# Cell_Temp_Controller_v1_0.net
KiCad netlist of a schematic drawn in EAGLE
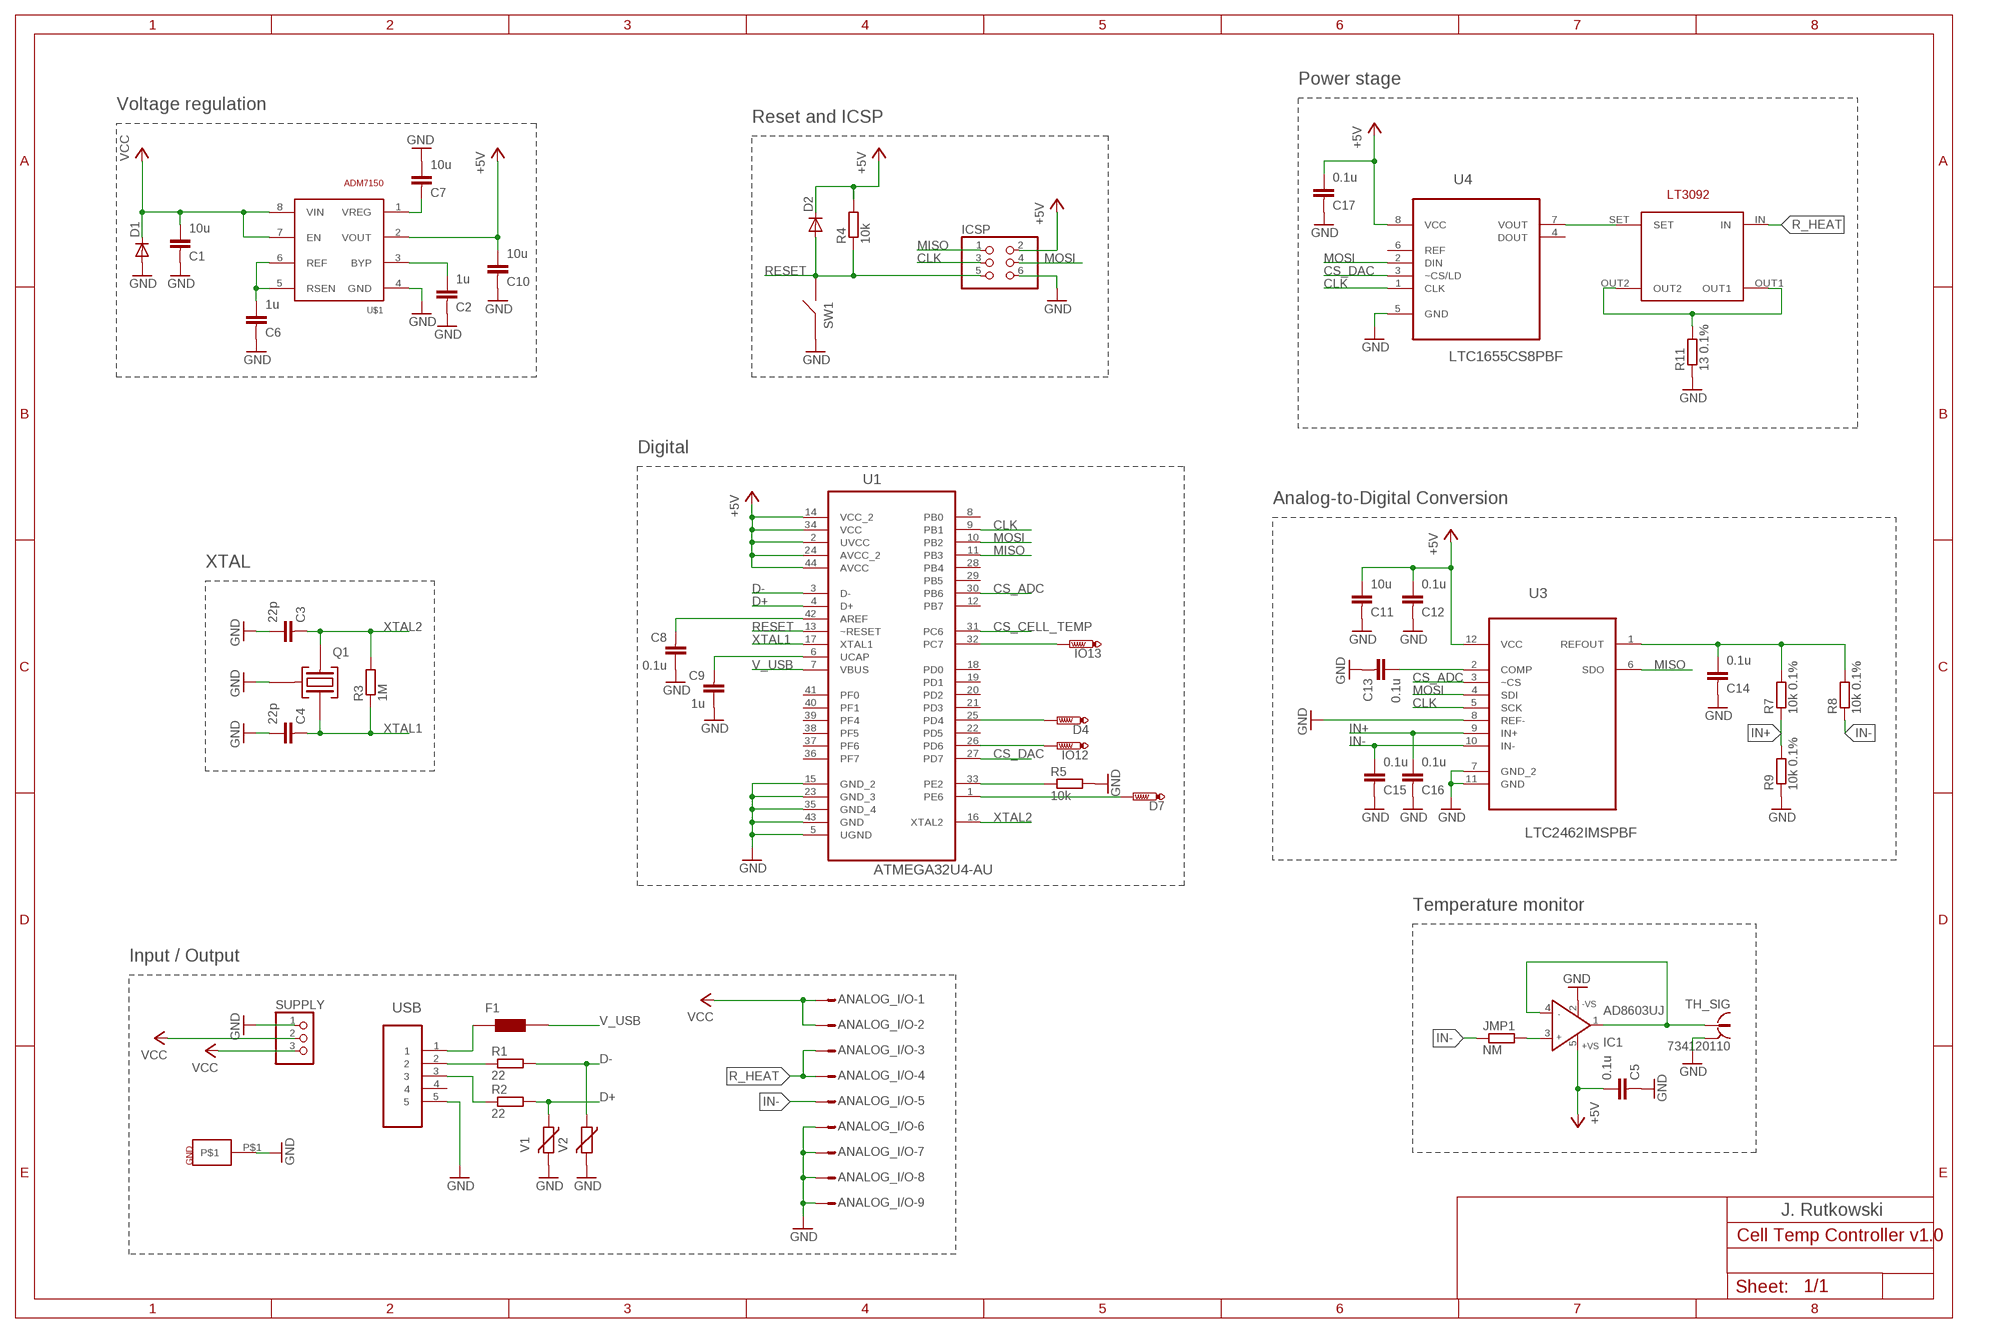
[diagram p0: schematic, sheet 1]

(export (version "E")
  (design (tool "Eeschema 10.0.6"))
  (components
    (comp (ref "ANALOG_I/O")
      (value "M09HPS")
      (footprint "eagle-import:M09HP")
      (libsource (lib "eagle-import") (part "M09?SHP"))
    )
    (comp (ref "C1")
      (value "10u")
      (footprint "eagle-import:C0603K")
      (libsource (lib "eagle-import") (part "C-EUC0603K"))
    )
    (comp (ref "C2")
      (value "1u")
      (footprint "eagle-import:C0603K")
      (libsource (lib "eagle-import") (part "C-EUC0603K"))
    )
    (comp (ref "C3")
      (value "22p")
      (footprint "eagle-import:C0603K")
      (libsource (lib "eagle-import") (part "C-EUC0603K"))
    )
    (comp (ref "C4")
      (value "22p")
      (footprint "eagle-import:C0603K")
      (libsource (lib "eagle-import") (part "C-EUC0603K"))
    )
    (comp (ref "C5")
      (value "0.1u")
      (footprint "eagle-import:C0603K")
      (libsource (lib "eagle-import") (part "C-EUC0603K"))
    )
    (comp (ref "C6")
      (value "1u")
      (footprint "eagle-import:C0603K")
      (libsource (lib "eagle-import") (part "C-EUC0603K"))
    )
    (comp (ref "C7")
      (value "10u")
      (footprint "eagle-import:C0603K")
      (libsource (lib "eagle-import") (part "C-EUC0603K"))
    )
    (comp (ref "C8")
      (value "0.1u")
      (footprint "eagle-import:C0603K")
      (libsource (lib "eagle-import") (part "C-EUC0603K"))
    )
    (comp (ref "C9")
      (value "1u")
      (footprint "eagle-import:C0603K")
      (libsource (lib "eagle-import") (part "C-EUC0603K"))
    )
    (comp (ref "C10")
      (value "10u")
      (footprint "eagle-import:C0603K")
      (libsource (lib "eagle-import") (part "C-EUC0603K"))
    )
    (comp (ref "C11")
      (value "10u")
      (footprint "eagle-import:C0603K")
      (libsource (lib "eagle-import") (part "C-EUC0603K"))
    )
    (comp (ref "C12")
      (value "0.1u")
      (footprint "eagle-import:C0603K")
      (libsource (lib "eagle-import") (part "C-EUC0603K"))
    )
    (comp (ref "C13")
      (value "0.1u")
      (footprint "eagle-import:C0603K")
      (libsource (lib "eagle-import") (part "C-EUC0603K"))
    )
    (comp (ref "C14")
      (value "0.1u")
      (footprint "eagle-import:C0603K")
      (libsource (lib "eagle-import") (part "C-EUC0603K"))
    )
    (comp (ref "C15")
      (value "0.1u")
      (footprint "eagle-import:C0603K")
      (libsource (lib "eagle-import") (part "C-EUC0603K"))
    )
    (comp (ref "C16")
      (value "0.1u")
      (footprint "eagle-import:C0603K")
      (libsource (lib "eagle-import") (part "C-EUC0603K"))
    )
    (comp (ref "C17")
      (value "0.1u")
      (footprint "eagle-import:C0603K")
      (libsource (lib "eagle-import") (part "C-EUC0603K"))
    )
    (comp (ref "D1")
      (value "DIODE-SOD123")
      (footprint "eagle-import:SOD123")
      (libsource (lib "eagle-import") (part "DIODE-SOD123"))
    )
    (comp (ref "D2")
      (value "DIODE-SOD123")
      (footprint "eagle-import:SOD123")
      (libsource (lib "eagle-import") (part "DIODE-SOD123"))
    )
    (comp (ref "D4")
      (value "PTR1PAD1-13")
      (footprint "eagle-import:P1-13")
      (libsource (lib "eagle-import") (part "PTR1PAD1-13"))
    )
    (comp (ref "D7")
      (value "PTR1PAD1-13")
      (footprint "eagle-import:P1-13")
      (libsource (lib "eagle-import") (part "PTR1PAD1-13"))
    )
    (comp (ref "F1")
      (value "FUSE")
      (footprint "eagle-import:C1812")
      (libsource (lib "eagle-import") (part "FUSE"))
    )
    (comp (ref "IC1")
      (value "AD8603UJ")
      (footprint "eagle-import:SOT23-5")
      (fields (field (name "MF") "ALTERA CORPORATION") (field (name "MPN") "AD8603AUJZ-REEL7"))
      (libsource (lib "eagle-import") (part "AD8603UJ"))
    )
    (comp (ref "ICSP")
      (value "PINHD-2X3")
      (footprint "eagle-import:2X03")
      (libsource (lib "eagle-import") (part "PINHD-2X3"))
    )
    (comp (ref "IO12")
      (value "PTR1PAD1-13")
      (footprint "eagle-import:P1-13")
      (libsource (lib "eagle-import") (part "PTR1PAD1-13"))
    )
    (comp (ref "IO13")
      (value "PTR1PAD1-13")
      (footprint "eagle-import:P1-13")
      (libsource (lib "eagle-import") (part "PTR1PAD1-13"))
    )
    (comp (ref "JMP1")
      (value "NM")
      (footprint "eagle-import:R0402")
      (libsource (lib "eagle-import") (part "R-EU_R0402"))
    )
    (comp (ref "Q1")
      (value "CX2520SB")
      (footprint "eagle-import:QUARTZ")
      (fields (field (name "MPN") "CX5032SB16000F0FLJZZ"))
      (libsource (lib "eagle-import") (part "CX2520SB"))
    )
    (comp (ref "R1")
      (value "22")
      (footprint "eagle-import:R0603")
      (libsource (lib "eagle-import") (part "R-EU_R0603"))
    )
    (comp (ref "R2")
      (value "22")
      (footprint "eagle-import:R0603")
      (libsource (lib "eagle-import") (part "R-EU_R0603"))
    )
    (comp (ref "R3")
      (value "1M")
      (footprint "eagle-import:R0603")
      (libsource (lib "eagle-import") (part "R-EU_R0603"))
    )
    (comp (ref "R4")
      (value "10k")
      (footprint "eagle-import:R0603")
      (libsource (lib "eagle-import") (part "R-EU_R0603"))
    )
    (comp (ref "R5")
      (value "10k")
      (footprint "eagle-import:R0603")
      (libsource (lib "eagle-import") (part "R-EU_R0603"))
    )
    (comp (ref "R7")
      (value "10k 0.1%")
      (footprint "eagle-import:R0603")
      (libsource (lib "eagle-import") (part "R-EU_R0603"))
    )
    (comp (ref "R8")
      (value "10k 0.1%")
      (footprint "eagle-import:R0603")
      (libsource (lib "eagle-import") (part "R-EU_R0603"))
    )
    (comp (ref "R9")
      (value "10k 0.1%")
      (footprint "eagle-import:R0603")
      (libsource (lib "eagle-import") (part "R-EU_R0603"))
    )
    (comp (ref "R11")
      (value "13 0.1%")
      (footprint "eagle-import:R2010")
      (libsource (lib "eagle-import") (part "R-EU_R2010"))
    )
    (comp (ref "SUPPLY")
      (value "PINHD-1X3")
      (footprint "eagle-import:1X03")
      (libsource (lib "eagle-import") (part "PINHD-1X3"))
    )
    (comp (ref "SW1")
      (value "B3U-1000P")
      (footprint "eagle-import:B3U-1000P")
      (fields (field (name "MPN") "B3U-1000P(M)"))
      (libsource (lib "eagle-import") (part "B3U-1000P"))
    )
    (comp (ref "TH_SIG")
      (value "734120110")
      (footprint "eagle-import:734120110")
      (libsource (lib "eagle-import") (part "734120110"))
    )
    (comp (ref "U$1")
      (value "ADM7150")
      (footprint "eagle-import:SO8")
      (libsource (lib "eagle-import") (part "ADM7150"))
    )
    (comp (ref "U$2")
      (value "LT3092")
      (footprint "eagle-import:SOT-223")
      (libsource (lib "eagle-import") (part "LT3092"))
    )
    (comp (ref "U$3")
      (value "GND_PAD")
      (footprint "eagle-import:GND_PAD")
      (libsource (lib "eagle-import") (part "GND_PAD"))
    )
    (comp (ref "U1")
      (value "ATMEGA32U4-AU")
      (footprint "eagle-import:QFP80P1200X1200X120-44N")
      (libsource (lib "eagle-import") (part "ATMEGA32U4-AU"))
    )
    (comp (ref "U3")
      (value "LTC2462IMSPBF")
      (footprint "eagle-import:SOP65P490X110-12N")
      (fields (field (name "MPN") "LTC2462IMS#PBF"))
      (libsource (lib "eagle-import") (part "LTC2462IMSPBF"))
    )
    (comp (ref "U4")
      (value "LTC1655CS8PBF")
      (footprint "eagle-import:SOIC127P600X175-8N")
      (fields (field (name "MPN") "LTC1655CS8#PBF"))
      (libsource (lib "eagle-import") (part "LTC1655CS8PBF"))
    )
    (comp (ref "USB")
      (value "47346-0001")
      (footprint "eagle-import:MOLEX_47346-0001")
      (libsource (lib "eagle-import") (part "47346-0001"))
    )
    (comp (ref "V1")
      (value "VARISTORCN0603")
      (footprint "eagle-import:CT_CN0603")
      (libsource (lib "eagle-import") (part "VARISTORCN0603"))
    )
    (comp (ref "V2")
      (value "VARISTORCN0603")
      (footprint "eagle-import:CT_CN0603")
      (libsource (lib "eagle-import") (part "VARISTORCN0603"))
    )
  )
  (nets
    (net (code "1") (name "+5V") (class "Default")
      (node (ref "C10") (pin "1") (pinfunction "1_1") (pintype "passive"))
      (node (ref "C11") (pin "1") (pinfunction "1_1") (pintype "passive"))
      (node (ref "C12") (pin "1") (pinfunction "1_1") (pintype "passive"))
      (node (ref "C17") (pin "1") (pinfunction "1_1") (pintype "passive"))
      (node (ref "C5") (pin "1") (pinfunction "1_1") (pintype "passive"))
      (node (ref "D2") (pin "C") (pinfunction "C_C") (pintype "passive"))
      (node (ref "IC1") (pin "5") (pinfunction "+VS_5") (pintype "input"))
      (node (ref "ICSP") (pin "2") (pinfunction "2_2") (pintype "passive"))
      (node (ref "R4") (pin "2") (pinfunction "2_2") (pintype "passive"))
      (node (ref "U$1") (pin "2") (pinfunction "VOUT_2") (pintype "bidirectional"))
      (node (ref "U1") (pin "14") (pinfunction "VCC_2_14") (pintype "power_in"))
      (node (ref "U1") (pin "2") (pinfunction "UVCC_2") (pintype "power_in"))
      (node (ref "U1") (pin "24") (pinfunction "AVCC_2_24") (pintype "power_in"))
      (node (ref "U1") (pin "34") (pinfunction "VCC_34") (pintype "power_in"))
      (node (ref "U1") (pin "44") (pinfunction "AVCC_44") (pintype "power_in"))
      (node (ref "U3") (pin "12") (pinfunction "VCC_12") (pintype "power_in"))
      (node (ref "U4") (pin "8") (pinfunction "VCC_8") (pintype "power_in"))
    )
    (net (code "2") (name "/CLK") (class "Default")
      (node (ref "ICSP") (pin "3") (pinfunction "3_3") (pintype "passive"))
      (node (ref "U1") (pin "9") (pinfunction "PB1_9") (pintype "bidirectional"))
      (node (ref "U3") (pin "5") (pinfunction "SCK_5") (pintype "input"))
      (node (ref "U4") (pin "1") (pinfunction "CLK_1") (pintype "input"))
    )
    (net (code "3") (name "/CS_ADC") (class "Default")
      (node (ref "U1") (pin "30") (pinfunction "PB6_30") (pintype "bidirectional"))
      (node (ref "U3") (pin "3") (pinfunction "~{CS}_3") (pintype "input"))
    )
    (net (code "4") (name "/CS_CELL_TEMP") (class "Default")
      (node (ref "U1") (pin "31") (pinfunction "PC6_31") (pintype "bidirectional"))
    )
    (net (code "5") (name "/CS_DAC") (class "Default")
      (node (ref "U1") (pin "27") (pinfunction "PD7_27") (pintype "bidirectional"))
      (node (ref "U4") (pin "3") (pinfunction "~{CS/LD}_3") (pintype "input"))
    )
    (net (code "6") (name "/D+") (class "Default")
      (node (ref "R2") (pin "2") (pinfunction "2_2") (pintype "passive"))
      (node (ref "U1") (pin "4") (pinfunction "D+_4") (pintype "passive"))
      (node (ref "V1") (pin "1") (pinfunction "1_1") (pintype "passive"))
    )
    (net (code "7") (name "/D-") (class "Default")
      (node (ref "R1") (pin "2") (pinfunction "2_2") (pintype "passive"))
      (node (ref "U1") (pin "3") (pinfunction "D-_3") (pintype "passive"))
      (node (ref "V2") (pin "1") (pinfunction "1_1") (pintype "passive"))
    )
    (net (code "8") (name "/MISO") (class "Default")
      (node (ref "ICSP") (pin "1") (pinfunction "1_1") (pintype "passive"))
      (node (ref "U1") (pin "11") (pinfunction "PB3_11") (pintype "bidirectional"))
      (node (ref "U3") (pin "6") (pinfunction "SDO_6") (pintype "output"))
    )
    (net (code "9") (name "/MOSI") (class "Default")
      (node (ref "ICSP") (pin "4") (pinfunction "4_4") (pintype "passive"))
      (node (ref "U1") (pin "10") (pinfunction "PB2_10") (pintype "bidirectional"))
      (node (ref "U3") (pin "4") (pinfunction "SDI_4") (pintype "input"))
      (node (ref "U4") (pin "2") (pinfunction "DIN_2") (pintype "input"))
    )
    (net (code "10") (name "/RESET") (class "Default")
      (node (ref "D2") (pin "A") (pinfunction "A_A") (pintype "passive"))
      (node (ref "ICSP") (pin "5") (pinfunction "5_5") (pintype "passive"))
      (node (ref "R4") (pin "1") (pinfunction "1_1") (pintype "passive"))
      (node (ref "SW1") (pin "2") (pinfunction "2_2") (pintype "bidirectional"))
      (node (ref "U1") (pin "13") (pinfunction "~{RESET}_13") (pintype "input"))
    )
    (net (code "11") (name "/V_USB") (class "Default")
      (node (ref "F1") (pin "1") (pinfunction "XTAL1_1") (pintype "bidirectional"))
      (node (ref "U1") (pin "7") (pinfunction "VBUS_7") (pintype "input"))
    )
    (net (code "12") (name "/XTAL1") (class "Default")
      (node (ref "C4") (pin "2") (pinfunction "2_2") (pintype "passive"))
      (node (ref "Q1") (pin "3") (pinfunction "XTAL2_3") (pintype "bidirectional"))
      (node (ref "R3") (pin "1") (pinfunction "1_1") (pintype "passive"))
      (node (ref "U1") (pin "17") (pinfunction "XTAL1_17") (pintype "input"))
    )
    (net (code "13") (name "/XTAL2") (class "Default")
      (node (ref "C3") (pin "2") (pinfunction "2_2") (pintype "passive"))
      (node (ref "Q1") (pin "1") (pinfunction "XTAL1_1") (pintype "bidirectional"))
      (node (ref "R3") (pin "2") (pinfunction "2_2") (pintype "passive"))
      (node (ref "U1") (pin "16") (pinfunction "XTAL2_16") (pintype "output"))
    )
    (net (code "14") (name "GND") (class "Default")
      (node (ref "ANALOG_I/O") (pin "6") (pinfunction "M_6") (pintype "passive"))
      (node (ref "ANALOG_I/O") (pin "7") (pinfunction "M_7") (pintype "passive"))
      (node (ref "ANALOG_I/O") (pin "8") (pinfunction "M_8") (pintype "passive"))
      (node (ref "ANALOG_I/O") (pin "9") (pinfunction "M_9") (pintype "passive"))
      (node (ref "C1") (pin "2") (pinfunction "2_2") (pintype "passive"))
      (node (ref "C10") (pin "2") (pinfunction "2_2") (pintype "passive"))
      (node (ref "C11") (pin "2") (pinfunction "2_2") (pintype "passive"))
      (node (ref "C12") (pin "2") (pinfunction "2_2") (pintype "passive"))
      (node (ref "C13") (pin "2") (pinfunction "2_2") (pintype "passive"))
      (node (ref "C14") (pin "2") (pinfunction "2_2") (pintype "passive"))
      (node (ref "C15") (pin "2") (pinfunction "2_2") (pintype "passive"))
      (node (ref "C16") (pin "2") (pinfunction "2_2") (pintype "passive"))
      (node (ref "C17") (pin "2") (pinfunction "2_2") (pintype "passive"))
      (node (ref "C2") (pin "2") (pinfunction "2_2") (pintype "passive"))
      (node (ref "C3") (pin "1") (pinfunction "1_1") (pintype "passive"))
      (node (ref "C4") (pin "1") (pinfunction "1_1") (pintype "passive"))
      (node (ref "C5") (pin "2") (pinfunction "2_2") (pintype "passive"))
      (node (ref "C6") (pin "2") (pinfunction "2_2") (pintype "passive"))
      (node (ref "C7") (pin "1") (pinfunction "1_1") (pintype "passive"))
      (node (ref "C8") (pin "1") (pinfunction "1_1") (pintype "passive"))
      (node (ref "C9") (pin "1") (pinfunction "1_1") (pintype "passive"))
      (node (ref "D1") (pin "A") (pinfunction "A_A") (pintype "passive"))
      (node (ref "IC1") (pin "2") (pinfunction "-VS_2") (pintype "input"))
      (node (ref "ICSP") (pin "6") (pinfunction "6_6") (pintype "passive"))
      (node (ref "Q1") (pin "2") (pinfunction "GND_2") (pintype "bidirectional"))
      (node (ref "R11") (pin "1") (pinfunction "1_1") (pintype "passive"))
      (node (ref "R5") (pin "2") (pinfunction "2_2") (pintype "passive"))
      (node (ref "R9") (pin "1") (pinfunction "1_1") (pintype "passive"))
      (node (ref "SUPPLY") (pin "1") (pinfunction "1_1") (pintype "passive"))
      (node (ref "SW1") (pin "1") (pinfunction "1_1") (pintype "bidirectional"))
      (node (ref "TH_SIG") (pin "S@1") (pinfunction "2_S@1") (pintype "passive"))
      (node (ref "TH_SIG") (pin "S@2") (pinfunction "2_S@2") (pintype "passive"))
      (node (ref "TH_SIG") (pin "S@3") (pinfunction "2_S@3") (pintype "passive"))
      (node (ref "U$1") (pin "4") (pinfunction "GND_4") (pintype "bidirectional"))
      (node (ref "U$3") (pin "P$1") (pinfunction "P$1_P$1") (pintype "bidirectional"))
      (node (ref "U1") (pin "15") (pinfunction "GND_2_15") (pintype "passive"))
      (node (ref "U1") (pin "23") (pinfunction "GND_3_23") (pintype "passive"))
      (node (ref "U1") (pin "35") (pinfunction "GND_4_35") (pintype "passive"))
      (node (ref "U1") (pin "43") (pinfunction "GND_43") (pintype "passive"))
      (node (ref "U1") (pin "5") (pinfunction "UGND_5") (pintype "passive"))
      (node (ref "U3") (pin "11") (pinfunction "GND_11") (pintype "passive"))
      (node (ref "U3") (pin "7") (pinfunction "GND_2_7") (pintype "passive"))
      (node (ref "U3") (pin "8") (pinfunction "REF-_8") (pintype "input"))
      (node (ref "U4") (pin "5") (pinfunction "GND_5") (pintype "passive"))
      (node (ref "USB") (pin "5") (pinfunction "5_5") (pintype "input"))
      (node (ref "V1") (pin "2") (pinfunction "2_2") (pintype "passive"))
      (node (ref "V2") (pin "2") (pinfunction "2_2") (pintype "passive"))
    )
    (net (code "15") (name "IN+") (class "Default")
      (node (ref "C16") (pin "1") (pinfunction "1_1") (pintype "passive"))
      (node (ref "R7") (pin "1") (pinfunction "1_1") (pintype "passive"))
      (node (ref "R9") (pin "2") (pinfunction "2_2") (pintype "passive"))
      (node (ref "U3") (pin "9") (pinfunction "IN+_9") (pintype "input"))
    )
    (net (code "16") (name "IN-") (class "Default")
      (node (ref "ANALOG_I/O") (pin "5") (pinfunction "M_5") (pintype "passive"))
      (node (ref "C15") (pin "1") (pinfunction "1_1") (pintype "passive"))
      (node (ref "JMP1") (pin "1") (pinfunction "1_1") (pintype "passive"))
      (node (ref "R8") (pin "1") (pinfunction "1_1") (pintype "passive"))
      (node (ref "U3") (pin "10") (pinfunction "IN-_10") (pintype "input"))
    )
    (net (code "17") (name "Net-(F1-XTAL2)") (class "Default")
      (node (ref "F1") (pin "2") (pinfunction "XTAL2_2") (pintype "bidirectional"))
      (node (ref "USB") (pin "1") (pinfunction "1_1") (pintype "input"))
    )
    (net (code "18") (name "Net-(IC1-IN+)") (class "Default")
      (node (ref "IC1") (pin "3") (pinfunction "IN+_3") (pintype "input"))
      (node (ref "JMP1") (pin "2") (pinfunction "2_2") (pintype "passive"))
    )
    (net (code "19") (name "Net-(IC1-IN-)") (class "Default")
      (node (ref "IC1") (pin "1") (pinfunction "OUT_1") (pintype "output"))
      (node (ref "IC1") (pin "4") (pinfunction "IN-_4") (pintype "input"))
      (node (ref "TH_SIG") (pin "1") (pinfunction "1_1") (pintype "passive"))
    )
    (net (code "20") (name "Net-(R1-Pad1)") (class "Default")
      (node (ref "R1") (pin "1") (pinfunction "1_1") (pintype "passive"))
      (node (ref "USB") (pin "2") (pinfunction "2_2") (pintype "input"))
    )
    (net (code "21") (name "Net-(R2-Pad1)") (class "Default")
      (node (ref "R2") (pin "1") (pinfunction "1_1") (pintype "passive"))
      (node (ref "USB") (pin "3") (pinfunction "3_3") (pintype "input"))
    )
    (net (code "22") (name "Net-(R11-Pad2)") (class "Default")
      (node (ref "R11") (pin "2") (pinfunction "2_2") (pintype "passive"))
      (node (ref "U$2") (pin "OUT1") (pinfunction "OUT1_OUT1") (pintype "bidirectional"))
      (node (ref "U$2") (pin "OUT2") (pinfunction "OUT2_OUT2") (pintype "bidirectional"))
    )
    (net (code "23") (name "Net-(U$1-BYP)") (class "Default")
      (node (ref "C2") (pin "1") (pinfunction "1_1") (pintype "passive"))
      (node (ref "U$1") (pin "3") (pinfunction "BYP_3") (pintype "bidirectional"))
    )
    (net (code "24") (name "Net-(U$1-REF)") (class "Default")
      (node (ref "C6") (pin "1") (pinfunction "1_1") (pintype "passive"))
      (node (ref "U$1") (pin "5") (pinfunction "RSEN_5") (pintype "bidirectional"))
      (node (ref "U$1") (pin "6") (pinfunction "REF_6") (pintype "bidirectional"))
    )
    (net (code "25") (name "Net-(U$1-VREG)") (class "Default")
      (node (ref "C7") (pin "2") (pinfunction "2_2") (pintype "passive"))
      (node (ref "U$1") (pin "1") (pinfunction "VREG_1") (pintype "bidirectional"))
    )
    (net (code "26") (name "Net-(U1-AREF)") (class "Default")
      (node (ref "C8") (pin "2") (pinfunction "2_2") (pintype "passive"))
      (node (ref "U1") (pin "42") (pinfunction "AREF_42") (pintype "input"))
    )
    (net (code "27") (name "Net-(U1-PC7)") (class "Default")
      (node (ref "IO13") (pin "TP") (pinfunction "TP_TP") (pintype "input"))
      (node (ref "U1") (pin "32") (pinfunction "PC7_32") (pintype "bidirectional"))
    )
    (net (code "28") (name "Net-(U1-PD4)") (class "Default")
      (node (ref "D4") (pin "TP") (pinfunction "TP_TP") (pintype "input"))
      (node (ref "U1") (pin "25") (pinfunction "PD4_25") (pintype "bidirectional"))
    )
    (net (code "29") (name "Net-(U1-PD6)") (class "Default")
      (node (ref "IO12") (pin "TP") (pinfunction "TP_TP") (pintype "input"))
      (node (ref "U1") (pin "26") (pinfunction "PD6_26") (pintype "bidirectional"))
    )
    (net (code "30") (name "Net-(U1-PE2)") (class "Default")
      (node (ref "R5") (pin "1") (pinfunction "1_1") (pintype "passive"))
      (node (ref "U1") (pin "33") (pinfunction "PE2_33") (pintype "bidirectional"))
    )
    (net (code "31") (name "Net-(U1-PE6)") (class "Default")
      (node (ref "D7") (pin "TP") (pinfunction "TP_TP") (pintype "input"))
      (node (ref "U1") (pin "1") (pinfunction "PE6_1") (pintype "bidirectional"))
    )
    (net (code "32") (name "Net-(U1-UCAP)") (class "Default")
      (node (ref "C9") (pin "2") (pinfunction "2_2") (pintype "passive"))
      (node (ref "U1") (pin "6") (pinfunction "UCAP_6") (pintype "power_in"))
    )
    (net (code "33") (name "Net-(U3-COMP)") (class "Default")
      (node (ref "C13") (pin "1") (pinfunction "1_1") (pintype "passive"))
      (node (ref "U3") (pin "2") (pinfunction "COMP_2") (pintype "passive"))
    )
    (net (code "34") (name "Net-(U3-REFOUT)") (class "Default")
      (node (ref "C14") (pin "1") (pinfunction "1_1") (pintype "passive"))
      (node (ref "R7") (pin "2") (pinfunction "2_2") (pintype "passive"))
      (node (ref "R8") (pin "2") (pinfunction "2_2") (pintype "passive"))
      (node (ref "U3") (pin "1") (pinfunction "REFOUT_1") (pintype "output"))
    )
    (net (code "35") (name "Net-(U4-VOUT)") (class "Default")
      (node (ref "U$2") (pin "SET") (pinfunction "SET_SET") (pintype "bidirectional"))
      (node (ref "U4") (pin "7") (pinfunction "VOUT_7") (pintype "output"))
    )
    (net (code "36") (name "R_HEAT") (class "Default")
      (node (ref "ANALOG_I/O") (pin "3") (pinfunction "M_3") (pintype "passive"))
      (node (ref "ANALOG_I/O") (pin "4") (pinfunction "M_4") (pintype "passive"))
      (node (ref "U$2") (pin "IN") (pinfunction "IN_IN") (pintype "bidirectional"))
    )
    (net (code "37") (name "VCC") (class "Default")
      (node (ref "ANALOG_I/O") (pin "1") (pinfunction "M_1") (pintype "passive"))
      (node (ref "ANALOG_I/O") (pin "2") (pinfunction "M_2") (pintype "passive"))
      (node (ref "C1") (pin "1") (pinfunction "1_1") (pintype "passive"))
      (node (ref "D1") (pin "C") (pinfunction "C_C") (pintype "passive"))
      (node (ref "SUPPLY") (pin "2") (pinfunction "2_2") (pintype "passive"))
      (node (ref "SUPPLY") (pin "3") (pinfunction "3_3") (pintype "passive"))
      (node (ref "U$1") (pin "7") (pinfunction "EN_7") (pintype "bidirectional"))
      (node (ref "U$1") (pin "8") (pinfunction "VIN_8") (pintype "bidirectional"))
    )
    (net (code "38") (name "unconnected-(U1-PB0-Pad8)") (class "Default")
      (node (ref "U1") (pin "8") (pinfunction "PB0_8") (pintype "bidirectional"))
    )
    (net (code "39") (name "unconnected-(U1-PB4-Pad28)") (class "Default")
      (node (ref "U1") (pin "28") (pinfunction "PB4_28") (pintype "bidirectional"))
    )
    (net (code "40") (name "unconnected-(U1-PB5-Pad29)") (class "Default")
      (node (ref "U1") (pin "29") (pinfunction "PB5_29") (pintype "bidirectional"))
    )
    (net (code "41") (name "unconnected-(U1-PB7-Pad12)") (class "Default")
      (node (ref "U1") (pin "12") (pinfunction "PB7_12") (pintype "bidirectional"))
    )
    (net (code "42") (name "unconnected-(U1-PD0-Pad18)") (class "Default")
      (node (ref "U1") (pin "18") (pinfunction "PD0_18") (pintype "bidirectional"))
    )
    (net (code "43") (name "unconnected-(U1-PD1-Pad19)") (class "Default")
      (node (ref "U1") (pin "19") (pinfunction "PD1_19") (pintype "bidirectional"))
    )
    (net (code "44") (name "unconnected-(U1-PD2-Pad20)") (class "Default")
      (node (ref "U1") (pin "20") (pinfunction "PD2_20") (pintype "bidirectional"))
    )
    (net (code "45") (name "unconnected-(U1-PD3-Pad21)") (class "Default")
      (node (ref "U1") (pin "21") (pinfunction "PD3_21") (pintype "bidirectional"))
    )
    (net (code "46") (name "unconnected-(U1-PD5-Pad22)") (class "Default")
      (node (ref "U1") (pin "22") (pinfunction "PD5_22") (pintype "bidirectional"))
    )
    (net (code "47") (name "unconnected-(U1-PF0-Pad41)") (class "Default")
      (node (ref "U1") (pin "41") (pinfunction "PF0_41") (pintype "bidirectional"))
    )
    (net (code "48") (name "unconnected-(U1-PF1-Pad40)") (class "Default")
      (node (ref "U1") (pin "40") (pinfunction "PF1_40") (pintype "bidirectional"))
    )
    (net (code "49") (name "unconnected-(U1-PF4-Pad39)") (class "Default")
      (node (ref "U1") (pin "39") (pinfunction "PF4_39") (pintype "bidirectional"))
    )
    (net (code "50") (name "unconnected-(U1-PF5-Pad38)") (class "Default")
      (node (ref "U1") (pin "38") (pinfunction "PF5_38") (pintype "bidirectional"))
    )
    (net (code "51") (name "unconnected-(U1-PF6-Pad37)") (class "Default")
      (node (ref "U1") (pin "37") (pinfunction "PF6_37") (pintype "bidirectional"))
    )
    (net (code "52") (name "unconnected-(U1-PF7-Pad36)") (class "Default")
      (node (ref "U1") (pin "36") (pinfunction "PF7_36") (pintype "bidirectional"))
    )
    (net (code "53") (name "unconnected-(U4-DOUT-Pad4)") (class "Default")
      (node (ref "U4") (pin "4") (pinfunction "DOUT_4") (pintype "output"))
    )
    (net (code "54") (name "unconnected-(U4-REF-Pad6)") (class "Default")
      (node (ref "U4") (pin "6") (pinfunction "REF_6") (pintype "input"))
    )
    (net (code "55") (name "unconnected-(USB-Pad4)") (class "Default")
      (node (ref "USB") (pin "4") (pinfunction "4_4") (pintype "input"))
    )
  )
)
